# main.net
KiCad netlist of a schematic drawn in EAGLE
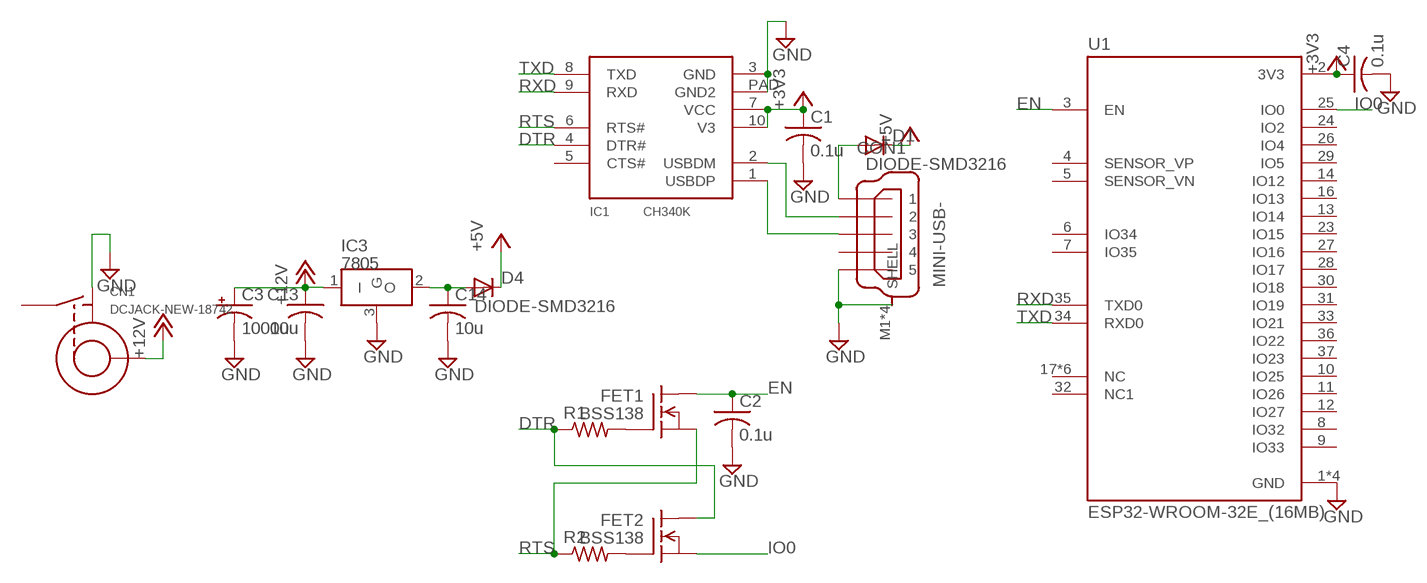
[diagram p0: schematic, sheet 1]

(export (version "E")
  (design (tool "Eeschema 10.0.6"))
  (components
    (comp (ref "C1")
      (value "0.1u")
      (footprint "eagle-import:2012-C")
      (libsource (lib "eagle-import") (part "C-2012"))
    )
    (comp (ref "C2")
      (value "0.1u")
      (footprint "eagle-import:2012-C")
      (fields (field (name "SPICEPREFIX") "C"))
      (libsource (lib "eagle-import") (part "C-2012"))
    )
    (comp (ref "C3")
      (value "1000u")
      (footprint "eagle-import:E2,5-8")
      (libsource (lib "eagle-import") (part "CC-2.5-8"))
    )
    (comp (ref "C4")
      (value "0.1u")
      (footprint "eagle-import:2012-C")
      (fields (field (name "SPICEPREFIX") "C"))
      (libsource (lib "eagle-import") (part "C-2012"))
    )
    (comp (ref "C13")
      (value "10u")
      (footprint "eagle-import:3216")
      (libsource (lib "eagle-import") (part "C-3216"))
    )
    (comp (ref "C14")
      (value "10u")
      (footprint "eagle-import:3216")
      (libsource (lib "eagle-import") (part "C-3216"))
    )
    (comp (ref "CN1")
      (value "DCJACK-NEW-18742")
      (footprint "eagle-import:18742")
      (libsource (lib "eagle-import") (part "DCJACK-NEW-18742"))
    )
    (comp (ref "CON1")
      (value "MINI-USB-")
      (footprint "eagle-import:UX60A-MB-5ST")
      (libsource (lib "eagle-import") (part "MINI-USB-"))
    )
    (comp (ref "D1")
      (value "DIODE-SMD3216")
      (footprint "eagle-import:D3216")
      (libsource (lib "eagle-import") (part "DIODE-SMD3216"))
    )
    (comp (ref "D4")
      (value "DIODE-SMD3216")
      (footprint "eagle-import:D3216")
      (libsource (lib "eagle-import") (part "DIODE-SMD3216"))
    )
    (comp (ref "FET1")
      (value "BSS138")
      (footprint "eagle-import:SOT23")
      (fields (field (name "SPICEPREFIX") "J"))
      (libsource (lib "eagle-import") (part "BSS138"))
    )
    (comp (ref "FET2")
      (value "BSS138")
      (footprint "eagle-import:SOT23")
      (fields (field (name "SPICEPREFIX") "J"))
      (libsource (lib "eagle-import") (part "BSS138"))
    )
    (comp (ref "IC1")
      (value "CH340K")
      (footprint "eagle-import:HSSOP10")
      (libsource (lib "eagle-import") (part "CH340K"))
    )
    (comp (ref "IC3")
      (value "7805")
      (footprint "eagle-import:P-HSIP3_2.30A")
      (libsource (lib "eagle-import") (part "7805"))
    )
    (comp (ref "R1")
      (value "R-2012")
      (footprint "eagle-import:2012-R")
      (fields (field (name "SPICEPREFIX") "R"))
      (libsource (lib "eagle-import") (part "R-2012"))
    )
    (comp (ref "R2")
      (value "R-2012")
      (footprint "eagle-import:2012-R")
      (fields (field (name "SPICEPREFIX") "R"))
      (libsource (lib "eagle-import") (part "R-2012"))
    )
    (comp (ref "U1")
      (value "ESP32-WROOM-32E_(16MB)")
      (footprint "eagle-import:XCVR_ESP32-WROOM-32E_(16MB)")
      (fields (field (name "MF") "Espressif Systems") (field (name "MP") "ESP32-WROOM-32E (16MB)"))
      (libsource (lib "eagle-import") (part "ESP32-WROOM-32E_(16MB)"))
    )
  )
  (nets
    (net (code "1") (name "+3V3") (class "Default")
      (node (ref "C1") (pin "1") (pinfunction "1_1") (pintype "passive"))
      (node (ref "C4") (pin "1") (pinfunction "1_1") (pintype "passive"))
      (node (ref "IC1") (pin "10") (pinfunction "V3_10") (pintype "bidirectional"))
      (node (ref "IC1") (pin "7") (pinfunction "VCC_7") (pintype "bidirectional"))
      (node (ref "U1") (pin "2") (pinfunction "3V3_2") (pintype "power_in"))
    )
    (net (code "2") (name "+5V") (class "Default")
      (node (ref "D1") (pin "K") (pinfunction "C_K") (pintype "passive"))
      (node (ref "D4") (pin "K") (pinfunction "C_K") (pintype "passive"))
    )
    (net (code "3") (name "+12V") (class "Default")
      (node (ref "C13") (pin "1") (pinfunction "1_1") (pintype "passive"))
      (node (ref "C3") (pin "+") (pinfunction "+_+") (pintype "passive"))
      (node (ref "CN1") (pin "P$1") (pinfunction "CENTER_P$1") (pintype "passive"))
      (node (ref "IC3") (pin "1") (pinfunction "I_1") (pintype "power_in"))
    )
    (net (code "4") (name "/DTR") (class "Default")
      (node (ref "FET2") (pin "3") (pinfunction "D_3") (pintype "passive"))
      (node (ref "IC1") (pin "4") (pinfunction "DTR#_4") (pintype "bidirectional"))
      (node (ref "R1") (pin "1") (pinfunction "1_1") (pintype "passive"))
    )
    (net (code "5") (name "/EN") (class "Default")
      (node (ref "C2") (pin "1") (pinfunction "1_1") (pintype "passive"))
      (node (ref "FET1") (pin "3") (pinfunction "D_3") (pintype "passive"))
      (node (ref "U1") (pin "3") (pinfunction "EN_3") (pintype "input"))
    )
    (net (code "6") (name "/IO0") (class "Default")
      (node (ref "FET2") (pin "2") (pinfunction "S_2") (pintype "passive"))
      (node (ref "U1") (pin "25") (pinfunction "IO0_25") (pintype "bidirectional"))
    )
    (net (code "7") (name "/RTS") (class "Default")
      (node (ref "FET1") (pin "2") (pinfunction "S_2") (pintype "passive"))
      (node (ref "IC1") (pin "6") (pinfunction "RTS#_6") (pintype "bidirectional"))
      (node (ref "R2") (pin "1") (pinfunction "1_1") (pintype "passive"))
    )
    (net (code "8") (name "/RXD") (class "Default")
      (node (ref "IC1") (pin "9") (pinfunction "RXD_9") (pintype "bidirectional"))
      (node (ref "U1") (pin "35") (pinfunction "TXD0_35") (pintype "bidirectional"))
    )
    (net (code "9") (name "/TXD") (class "Default")
      (node (ref "IC1") (pin "8") (pinfunction "TXD_8") (pintype "bidirectional"))
      (node (ref "U1") (pin "34") (pinfunction "RXD0_34") (pintype "bidirectional"))
    )
    (net (code "10") (name "GND") (class "Default")
      (node (ref "C1") (pin "2") (pinfunction "2_2") (pintype "passive"))
      (node (ref "C13") (pin "2") (pinfunction "2_2") (pintype "passive"))
      (node (ref "C14") (pin "2") (pinfunction "2_2") (pintype "passive"))
      (node (ref "C2") (pin "2") (pinfunction "2_2") (pintype "passive"))
      (node (ref "C3") (pin "-") (pinfunction "-_-") (pintype "passive"))
      (node (ref "C4") (pin "2") (pinfunction "2_2") (pintype "passive"))
      (node (ref "CN1") (pin "P$2") (pinfunction "TIP_P$2") (pintype "passive"))
      (node (ref "CON1") (pin "5") (pinfunction "5_5") (pintype "input"))
      (node (ref "CON1") (pin "M1") (pinfunction "SHELL_M1") (pintype "bidirectional"))
      (node (ref "CON1") (pin "M2") (pinfunction "SHELL_M2") (pintype "bidirectional"))
      (node (ref "CON1") (pin "M3") (pinfunction "SHELL_M3") (pintype "bidirectional"))
      (node (ref "CON1") (pin "M4") (pinfunction "SHELL_M4") (pintype "bidirectional"))
      (node (ref "IC1") (pin "3") (pinfunction "GND_3") (pintype "bidirectional"))
      (node (ref "IC1") (pin "PAD") (pinfunction "GND2_PAD") (pintype "bidirectional"))
      (node (ref "IC3") (pin "3") (pinfunction "G_3") (pintype "power_in"))
      (node (ref "U1") (pin "1") (pinfunction "GND_1") (pintype "power_in"))
      (node (ref "U1") (pin "15") (pinfunction "GND_15") (pintype "power_in"))
      (node (ref "U1") (pin "38") (pinfunction "GND_38") (pintype "power_in"))
      (node (ref "U1") (pin "P$1") (pinfunction "GND_P$1") (pintype "power_in"))
    )
    (net (code "11") (name "Net-(CON1-Pad1)") (class "Default")
      (node (ref "CON1") (pin "1") (pinfunction "1_1") (pintype "input"))
      (node (ref "D1") (pin "A") (pinfunction "A_A") (pintype "passive"))
    )
    (net (code "12") (name "Net-(FET1-G)") (class "Default")
      (node (ref "FET1") (pin "1") (pinfunction "G_1") (pintype "passive"))
      (node (ref "R1") (pin "2") (pinfunction "2_2") (pintype "passive"))
    )
    (net (code "13") (name "Net-(FET2-G)") (class "Default")
      (node (ref "FET2") (pin "1") (pinfunction "G_1") (pintype "passive"))
      (node (ref "R2") (pin "2") (pinfunction "2_2") (pintype "passive"))
    )
    (net (code "14") (name "Net-(IC1-USBDM)") (class "Default")
      (node (ref "CON1") (pin "2") (pinfunction "2_2") (pintype "input"))
      (node (ref "IC1") (pin "2") (pinfunction "USBDM_2") (pintype "bidirectional"))
    )
    (net (code "15") (name "Net-(IC1-USBDP)") (class "Default")
      (node (ref "CON1") (pin "3") (pinfunction "3_3") (pintype "input"))
      (node (ref "IC1") (pin "1") (pinfunction "USBDP_1") (pintype "bidirectional"))
    )
    (net (code "16") (name "Net-(IC3-O)") (class "Default")
      (node (ref "C14") (pin "1") (pinfunction "1_1") (pintype "passive"))
      (node (ref "D4") (pin "A") (pinfunction "A_A") (pintype "passive"))
      (node (ref "IC3") (pin "2") (pinfunction "O_2") (pintype "power_in"))
    )
    (net (code "17") (name "unconnected-(CN1-SHUNT-PadP$3)") (class "Default")
      (node (ref "CN1") (pin "P$3") (pinfunction "SHUNT_P$3") (pintype "passive"))
    )
    (net (code "18") (name "unconnected-(CON1-Pad4)") (class "Default")
      (node (ref "CON1") (pin "4") (pinfunction "4_4") (pintype "input"))
    )
    (net (code "19") (name "unconnected-(IC1-CTS#-Pad5)") (class "Default")
      (node (ref "IC1") (pin "5") (pinfunction "CTS#_5") (pintype "bidirectional"))
    )
    (net (code "20") (name "unconnected-(U1-IO2-Pad24)") (class "Default")
      (node (ref "U1") (pin "24") (pinfunction "IO2_24") (pintype "bidirectional"))
    )
    (net (code "21") (name "unconnected-(U1-IO4-Pad26)") (class "Default")
      (node (ref "U1") (pin "26") (pinfunction "IO4_26") (pintype "bidirectional"))
    )
    (net (code "22") (name "unconnected-(U1-IO5-Pad29)") (class "Default")
      (node (ref "U1") (pin "29") (pinfunction "IO5_29") (pintype "bidirectional"))
    )
    (net (code "23") (name "unconnected-(U1-IO12-Pad14)") (class "Default")
      (node (ref "U1") (pin "14") (pinfunction "IO12_14") (pintype "bidirectional"))
    )
    (net (code "24") (name "unconnected-(U1-IO13-Pad16)") (class "Default")
      (node (ref "U1") (pin "16") (pinfunction "IO13_16") (pintype "bidirectional"))
    )
    (net (code "25") (name "unconnected-(U1-IO14-Pad13)") (class "Default")
      (node (ref "U1") (pin "13") (pinfunction "IO14_13") (pintype "bidirectional"))
    )
    (net (code "26") (name "unconnected-(U1-IO15-Pad23)") (class "Default")
      (node (ref "U1") (pin "23") (pinfunction "IO15_23") (pintype "bidirectional"))
    )
    (net (code "27") (name "unconnected-(U1-IO16-Pad27)") (class "Default")
      (node (ref "U1") (pin "27") (pinfunction "IO16_27") (pintype "bidirectional"))
    )
    (net (code "28") (name "unconnected-(U1-IO17-Pad28)") (class "Default")
      (node (ref "U1") (pin "28") (pinfunction "IO17_28") (pintype "bidirectional"))
    )
    (net (code "29") (name "unconnected-(U1-IO18-Pad30)") (class "Default")
      (node (ref "U1") (pin "30") (pinfunction "IO18_30") (pintype "bidirectional"))
    )
    (net (code "30") (name "unconnected-(U1-IO19-Pad31)") (class "Default")
      (node (ref "U1") (pin "31") (pinfunction "IO19_31") (pintype "bidirectional"))
    )
    (net (code "31") (name "unconnected-(U1-IO21-Pad33)") (class "Default")
      (node (ref "U1") (pin "33") (pinfunction "IO21_33") (pintype "bidirectional"))
    )
    (net (code "32") (name "unconnected-(U1-IO22-Pad36)") (class "Default")
      (node (ref "U1") (pin "36") (pinfunction "IO22_36") (pintype "bidirectional"))
    )
    (net (code "33") (name "unconnected-(U1-IO23-Pad37)") (class "Default")
      (node (ref "U1") (pin "37") (pinfunction "IO23_37") (pintype "bidirectional"))
    )
    (net (code "34") (name "unconnected-(U1-IO25-Pad10)") (class "Default")
      (node (ref "U1") (pin "10") (pinfunction "IO25_10") (pintype "bidirectional"))
    )
    (net (code "35") (name "unconnected-(U1-IO26-Pad11)") (class "Default")
      (node (ref "U1") (pin "11") (pinfunction "IO26_11") (pintype "bidirectional"))
    )
    (net (code "36") (name "unconnected-(U1-IO27-Pad12)") (class "Default")
      (node (ref "U1") (pin "12") (pinfunction "IO27_12") (pintype "bidirectional"))
    )
    (net (code "37") (name "unconnected-(U1-IO32-Pad8)") (class "Default")
      (node (ref "U1") (pin "8") (pinfunction "IO32_8") (pintype "bidirectional"))
    )
    (net (code "38") (name "unconnected-(U1-IO33-Pad9)") (class "Default")
      (node (ref "U1") (pin "9") (pinfunction "IO33_9") (pintype "bidirectional"))
    )
    (net (code "39") (name "unconnected-(U1-IO34-Pad6)") (class "Default")
      (node (ref "U1") (pin "6") (pinfunction "IO34_6") (pintype "input"))
    )
    (net (code "40") (name "unconnected-(U1-IO35-Pad7)") (class "Default")
      (node (ref "U1") (pin "7") (pinfunction "IO35_7") (pintype "input"))
    )
    (net (code "41") (name "unconnected-(U1-NC-Pad17)") (class "Default")
      (node (ref "U1") (pin "17") (pinfunction "NC_17") (pintype "no_connect"))
    )
    (net (code "42") (name "unconnected-(U1-NC-Pad18)") (class "Default")
      (node (ref "U1") (pin "18") (pinfunction "NC_18") (pintype "no_connect"))
    )
    (net (code "43") (name "unconnected-(U1-NC-Pad19)") (class "Default")
      (node (ref "U1") (pin "19") (pinfunction "NC_19") (pintype "no_connect"))
    )
    (net (code "44") (name "unconnected-(U1-NC-Pad20)") (class "Default")
      (node (ref "U1") (pin "20") (pinfunction "NC_20") (pintype "no_connect"))
    )
    (net (code "45") (name "unconnected-(U1-NC-Pad21)") (class "Default")
      (node (ref "U1") (pin "21") (pinfunction "NC_21") (pintype "no_connect"))
    )
    (net (code "46") (name "unconnected-(U1-NC-Pad22)") (class "Default")
      (node (ref "U1") (pin "22") (pinfunction "NC_22") (pintype "no_connect"))
    )
    (net (code "47") (name "unconnected-(U1-NC1-Pad32)") (class "Default")
      (node (ref "U1") (pin "32") (pinfunction "NC1_32") (pintype "no_connect"))
    )
    (net (code "48") (name "unconnected-(U1-SENSOR_VN-Pad5)") (class "Default")
      (node (ref "U1") (pin "5") (pinfunction "SENSOR_VN_5") (pintype "input"))
    )
    (net (code "49") (name "unconnected-(U1-SENSOR_VP-Pad4)") (class "Default")
      (node (ref "U1") (pin "4") (pinfunction "SENSOR_VP_4") (pintype "input"))
    )
  )
)
